# LCD_sterowanie.net
KiCad netlist of a schematic drawn in EAGLE
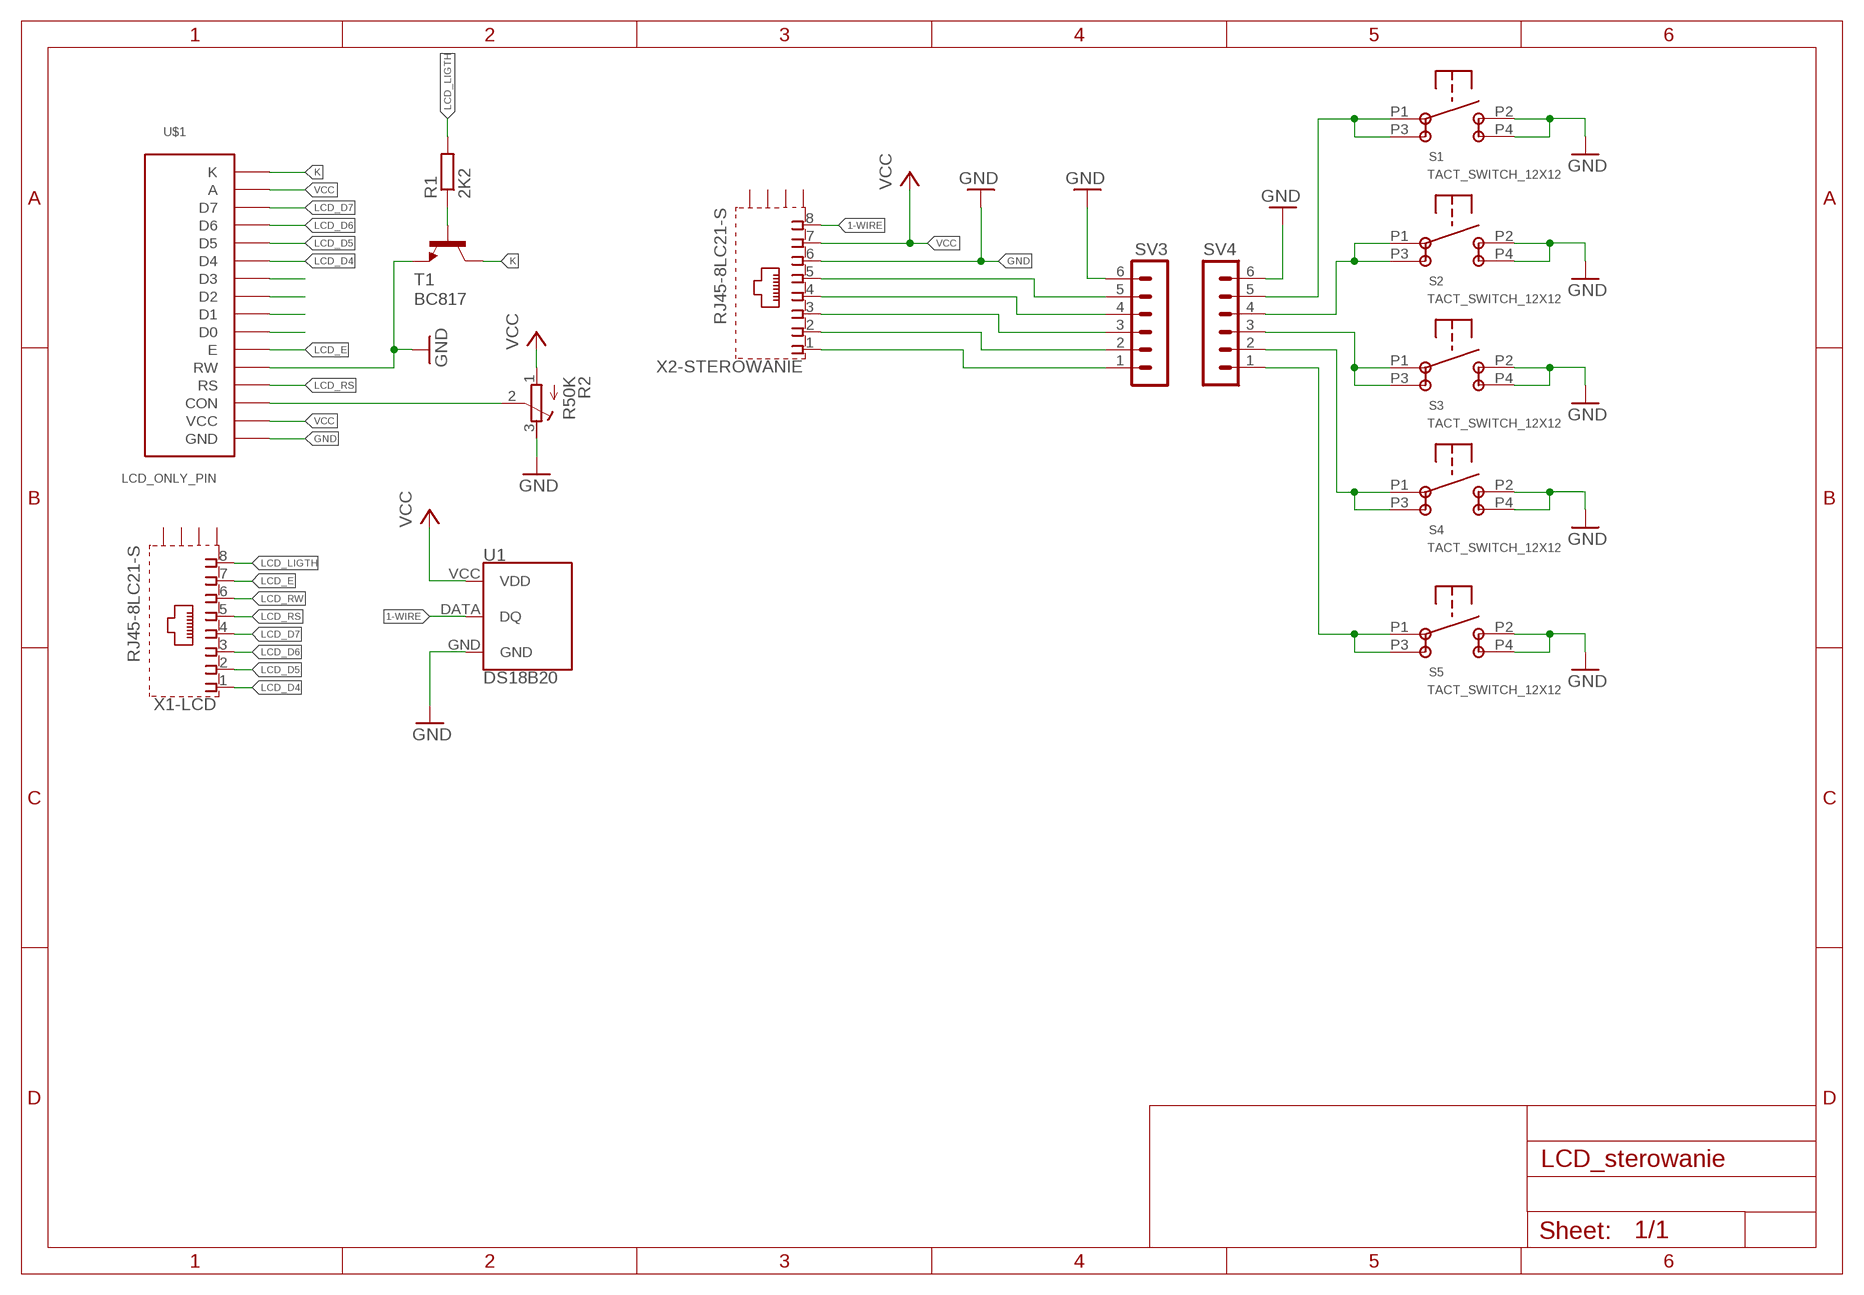
[diagram p0: schematic, sheet 1]

(export (version "E")
  (design (tool "Eeschema 10.0.6"))
  (components
    (comp (ref "R1")
      (value "2K2")
      (footprint "eagle-import:M0805")
      (libsource (lib "eagle-import") (part "R-EU_M0805"))
    )
    (comp (ref "R2")
      (value "R50K")
      (footprint "eagle-import:RTRIM3296P")
      (libsource (lib "eagle-import") (part "R-TRIMM3296P"))
    )
    (comp (ref "S1")
      (value "TACT_SWITCH_12X12")
      (footprint "eagle-import:TACT_SWITCH_12X12")
      (libsource (lib "eagle-import") (part "TACT_SWITCH_12X12"))
    )
    (comp (ref "S2")
      (value "TACT_SWITCH_12X12")
      (footprint "eagle-import:TACT_SWITCH_12X12")
      (libsource (lib "eagle-import") (part "TACT_SWITCH_12X12"))
    )
    (comp (ref "S3")
      (value "TACT_SWITCH_12X12")
      (footprint "eagle-import:TACT_SWITCH_12X12")
      (libsource (lib "eagle-import") (part "TACT_SWITCH_12X12"))
    )
    (comp (ref "S4")
      (value "TACT_SWITCH_12X12")
      (footprint "eagle-import:TACT_SWITCH_12X12")
      (libsource (lib "eagle-import") (part "TACT_SWITCH_12X12"))
    )
    (comp (ref "S5")
      (value "TACT_SWITCH_12X12")
      (footprint "eagle-import:TACT_SWITCH_12X12")
      (libsource (lib "eagle-import") (part "TACT_SWITCH_12X12"))
    )
    (comp (ref "SV3")
      (value "MA06-1")
      (footprint "eagle-import:MA06-1")
      (libsource (lib "eagle-import") (part "MA06-1"))
    )
    (comp (ref "SV4")
      (value "MA06-1")
      (footprint "eagle-import:MA06-1")
      (libsource (lib "eagle-import") (part "MA06-1"))
    )
    (comp (ref "T1")
      (value "BC817")
      (footprint "eagle-import:SOT23")
      (libsource (lib "eagle-import") (part "BC847"))
    )
    (comp (ref "U$1")
      (value "LCD_ONLY_PIN")
      (footprint "eagle-import:LCD_ONLY_PIN")
      (libsource (lib "eagle-import") (part "LCD_ONLY_PIN"))
    )
    (comp (ref "U1")
      (value "DS18B20")
      (footprint "eagle-import:TO-92-AMMO")
      (libsource (lib "eagle-import") (part "DS18B20"))
    )
    (comp (ref "X1-LCD")
      (value "RJ45-8LC21-S")
      (footprint "eagle-import:RJ45-SHIELD1")
      (libsource (lib "eagle-import") (part "RJ4521-S-8LC"))
    )
    (comp (ref "X2-STEROWANIE")
      (value "RJ45-8LC21-S")
      (footprint "eagle-import:RJ45-SHIELD1")
      (libsource (lib "eagle-import") (part "RJ4521-S-8LC"))
    )
  )
  (nets
    (net (code "1") (name "1-WIRE") (class "Default")
      (node (ref "U1") (pin "DATA") (pinfunction "DQ_DATA") (pintype "bidirectional"))
      (node (ref "X2-STEROWANIE") (pin "8") (pinfunction "8_8") (pintype "passive"))
    )
    (net (code "2") (name "GND") (class "Default")
      (node (ref "R2") (pin "3") (pinfunction "E_3") (pintype "passive"))
      (node (ref "S1") (pin "P2") (pinfunction "P$2_P2") (pintype "bidirectional"))
      (node (ref "S1") (pin "P4") (pinfunction "P$4_P4") (pintype "bidirectional"))
      (node (ref "S2") (pin "P2") (pinfunction "P$2_P2") (pintype "bidirectional"))
      (node (ref "S2") (pin "P4") (pinfunction "P$4_P4") (pintype "bidirectional"))
      (node (ref "S3") (pin "P2") (pinfunction "P$2_P2") (pintype "bidirectional"))
      (node (ref "S3") (pin "P4") (pinfunction "P$4_P4") (pintype "bidirectional"))
      (node (ref "S4") (pin "P2") (pinfunction "P$2_P2") (pintype "bidirectional"))
      (node (ref "S4") (pin "P4") (pinfunction "P$4_P4") (pintype "bidirectional"))
      (node (ref "S5") (pin "P2") (pinfunction "P$2_P2") (pintype "bidirectional"))
      (node (ref "S5") (pin "P4") (pinfunction "P$4_P4") (pintype "bidirectional"))
      (node (ref "SV3") (pin "6") (pinfunction "6_6") (pintype "passive"))
      (node (ref "SV4") (pin "6") (pinfunction "6_6") (pintype "passive"))
      (node (ref "T1") (pin "2") (pinfunction "E_2") (pintype "passive"))
      (node (ref "U$1") (pin "GND") (pinfunction "GND_GND") (pintype "bidirectional"))
      (node (ref "U$1") (pin "RW") (pinfunction "RW_RW") (pintype "bidirectional"))
      (node (ref "U1") (pin "GND") (pinfunction "GND_GND") (pintype "power_in"))
      (node (ref "X2-STEROWANIE") (pin "6") (pinfunction "6_6") (pintype "passive"))
    )
    (net (code "3") (name "K") (class "Default")
      (node (ref "T1") (pin "3") (pinfunction "C_3") (pintype "passive"))
      (node (ref "U$1") (pin "K") (pinfunction "K_K") (pintype "bidirectional"))
    )
    (net (code "4") (name "LCD_D4") (class "Default")
      (node (ref "U$1") (pin "D4") (pinfunction "D4_D4") (pintype "bidirectional"))
      (node (ref "X1-LCD") (pin "1") (pinfunction "1_1") (pintype "passive"))
    )
    (net (code "5") (name "LCD_D5") (class "Default")
      (node (ref "U$1") (pin "D5") (pinfunction "D5_D5") (pintype "bidirectional"))
      (node (ref "X1-LCD") (pin "2") (pinfunction "2_2") (pintype "passive"))
    )
    (net (code "6") (name "LCD_D6") (class "Default")
      (node (ref "U$1") (pin "D6") (pinfunction "D6_D6") (pintype "bidirectional"))
      (node (ref "X1-LCD") (pin "3") (pinfunction "3_3") (pintype "passive"))
    )
    (net (code "7") (name "LCD_D7") (class "Default")
      (node (ref "U$1") (pin "D7") (pinfunction "D7_D7") (pintype "bidirectional"))
      (node (ref "X1-LCD") (pin "4") (pinfunction "4_4") (pintype "passive"))
    )
    (net (code "8") (name "LCD_E") (class "Default")
      (node (ref "U$1") (pin "E") (pinfunction "E_E") (pintype "bidirectional"))
      (node (ref "X1-LCD") (pin "7") (pinfunction "7_7") (pintype "passive"))
    )
    (net (code "9") (name "LCD_LIGTH") (class "Default")
      (node (ref "R1") (pin "2") (pinfunction "2_2") (pintype "passive"))
      (node (ref "X1-LCD") (pin "8") (pinfunction "8_8") (pintype "passive"))
    )
    (net (code "10") (name "LCD_RS") (class "Default")
      (node (ref "U$1") (pin "RS") (pinfunction "RS_RS") (pintype "bidirectional"))
      (node (ref "X1-LCD") (pin "5") (pinfunction "5_5") (pintype "passive"))
    )
    (net (code "11") (name "LCD_RW") (class "Default")
      (node (ref "X1-LCD") (pin "6") (pinfunction "6_6") (pintype "passive"))
    )
    (net (code "12") (name "Net-(R2-S)") (class "Default")
      (node (ref "R2") (pin "2") (pinfunction "S_2") (pintype "passive"))
      (node (ref "U$1") (pin "CON") (pinfunction "CON_CON") (pintype "bidirectional"))
    )
    (net (code "13") (name "Net-(S1-P$1)") (class "Default")
      (node (ref "S1") (pin "P1") (pinfunction "P$1_P1") (pintype "bidirectional"))
      (node (ref "S1") (pin "P3") (pinfunction "P$3_P3") (pintype "bidirectional"))
      (node (ref "SV4") (pin "5") (pinfunction "5_5") (pintype "passive"))
    )
    (net (code "14") (name "Net-(S2-P$1)") (class "Default")
      (node (ref "S2") (pin "P1") (pinfunction "P$1_P1") (pintype "bidirectional"))
      (node (ref "S2") (pin "P3") (pinfunction "P$3_P3") (pintype "bidirectional"))
      (node (ref "SV4") (pin "4") (pinfunction "4_4") (pintype "passive"))
    )
    (net (code "15") (name "Net-(S3-P$1)") (class "Default")
      (node (ref "S3") (pin "P1") (pinfunction "P$1_P1") (pintype "bidirectional"))
      (node (ref "S3") (pin "P3") (pinfunction "P$3_P3") (pintype "bidirectional"))
      (node (ref "SV4") (pin "3") (pinfunction "3_3") (pintype "passive"))
    )
    (net (code "16") (name "Net-(S4-P$1)") (class "Default")
      (node (ref "S4") (pin "P1") (pinfunction "P$1_P1") (pintype "bidirectional"))
      (node (ref "S4") (pin "P3") (pinfunction "P$3_P3") (pintype "bidirectional"))
      (node (ref "SV4") (pin "2") (pinfunction "2_2") (pintype "passive"))
    )
    (net (code "17") (name "Net-(S5-P$1)") (class "Default")
      (node (ref "S5") (pin "P1") (pinfunction "P$1_P1") (pintype "bidirectional"))
      (node (ref "S5") (pin "P3") (pinfunction "P$3_P3") (pintype "bidirectional"))
      (node (ref "SV4") (pin "1") (pinfunction "1_1") (pintype "passive"))
    )
    (net (code "18") (name "Net-(SV3-Pad1)") (class "Default")
      (node (ref "SV3") (pin "1") (pinfunction "1_1") (pintype "passive"))
      (node (ref "X2-STEROWANIE") (pin "1") (pinfunction "1_1") (pintype "passive"))
    )
    (net (code "19") (name "Net-(SV3-Pad2)") (class "Default")
      (node (ref "SV3") (pin "2") (pinfunction "2_2") (pintype "passive"))
      (node (ref "X2-STEROWANIE") (pin "2") (pinfunction "2_2") (pintype "passive"))
    )
    (net (code "20") (name "Net-(SV3-Pad3)") (class "Default")
      (node (ref "SV3") (pin "3") (pinfunction "3_3") (pintype "passive"))
      (node (ref "X2-STEROWANIE") (pin "3") (pinfunction "3_3") (pintype "passive"))
    )
    (net (code "21") (name "Net-(SV3-Pad4)") (class "Default")
      (node (ref "SV3") (pin "4") (pinfunction "4_4") (pintype "passive"))
      (node (ref "X2-STEROWANIE") (pin "4") (pinfunction "4_4") (pintype "passive"))
    )
    (net (code "22") (name "Net-(SV3-Pad5)") (class "Default")
      (node (ref "SV3") (pin "5") (pinfunction "5_5") (pintype "passive"))
      (node (ref "X2-STEROWANIE") (pin "5") (pinfunction "5_5") (pintype "passive"))
    )
    (net (code "23") (name "Net-(T1-B)") (class "Default")
      (node (ref "R1") (pin "1") (pinfunction "1_1") (pintype "passive"))
      (node (ref "T1") (pin "1") (pinfunction "B_1") (pintype "passive"))
    )
    (net (code "24") (name "VCC") (class "Default")
      (node (ref "R2") (pin "1") (pinfunction "A_1") (pintype "passive"))
      (node (ref "U$1") (pin "A") (pinfunction "A_A") (pintype "bidirectional"))
      (node (ref "U$1") (pin "VCC") (pinfunction "VCC_VCC") (pintype "bidirectional"))
      (node (ref "U1") (pin "VCC") (pinfunction "VDD_VCC") (pintype "power_in"))
      (node (ref "X2-STEROWANIE") (pin "7") (pinfunction "7_7") (pintype "passive"))
    )
    (net (code "25") (name "unconnected-(U$1-PadD0)") (class "Default")
      (node (ref "U$1") (pin "D0") (pinfunction "D0_D0") (pintype "bidirectional"))
    )
    (net (code "26") (name "unconnected-(U$1-PadD1)") (class "Default")
      (node (ref "U$1") (pin "D1") (pinfunction "D1_D1") (pintype "bidirectional"))
    )
    (net (code "27") (name "unconnected-(U$1-PadD2)") (class "Default")
      (node (ref "U$1") (pin "D2") (pinfunction "D2_D2") (pintype "bidirectional"))
    )
    (net (code "28") (name "unconnected-(U$1-PadD3)") (class "Default")
      (node (ref "U$1") (pin "D3") (pinfunction "D3_D3") (pintype "bidirectional"))
    )
    (net (code "29") (name "unconnected-(X1-LCD-S-PadS1)") (class "Default")
      (node (ref "X1-LCD") (pin "S1") (pinfunction "S_S1") (pintype "passive"))
    )
    (net (code "30") (name "unconnected-(X1-LCD-S-PadS2)") (class "Default")
      (node (ref "X1-LCD") (pin "S2") (pinfunction "S_S2") (pintype "passive"))
    )
    (net (code "31") (name "unconnected-(X1-LCD-S-PadS3)") (class "Default")
      (node (ref "X1-LCD") (pin "S3") (pinfunction "S_S3") (pintype "passive"))
    )
    (net (code "32") (name "unconnected-(X1-LCD-S-PadS4)") (class "Default")
      (node (ref "X1-LCD") (pin "S4") (pinfunction "S_S4") (pintype "passive"))
    )
    (net (code "33") (name "unconnected-(X2-STEROWANIE-S-PadS1)") (class "Default")
      (node (ref "X2-STEROWANIE") (pin "S1") (pinfunction "S_S1") (pintype "passive"))
    )
    (net (code "34") (name "unconnected-(X2-STEROWANIE-S-PadS2)") (class "Default")
      (node (ref "X2-STEROWANIE") (pin "S2") (pinfunction "S_S2") (pintype "passive"))
    )
    (net (code "35") (name "unconnected-(X2-STEROWANIE-S-PadS3)") (class "Default")
      (node (ref "X2-STEROWANIE") (pin "S3") (pinfunction "S_S3") (pintype "passive"))
    )
    (net (code "36") (name "unconnected-(X2-STEROWANIE-S-PadS4)") (class "Default")
      (node (ref "X2-STEROWANIE") (pin "S4") (pinfunction "S_S4") (pintype "passive"))
    )
  )
)
